# Alim.net
KiCad netlist of a schematic drawn in Altium Designer
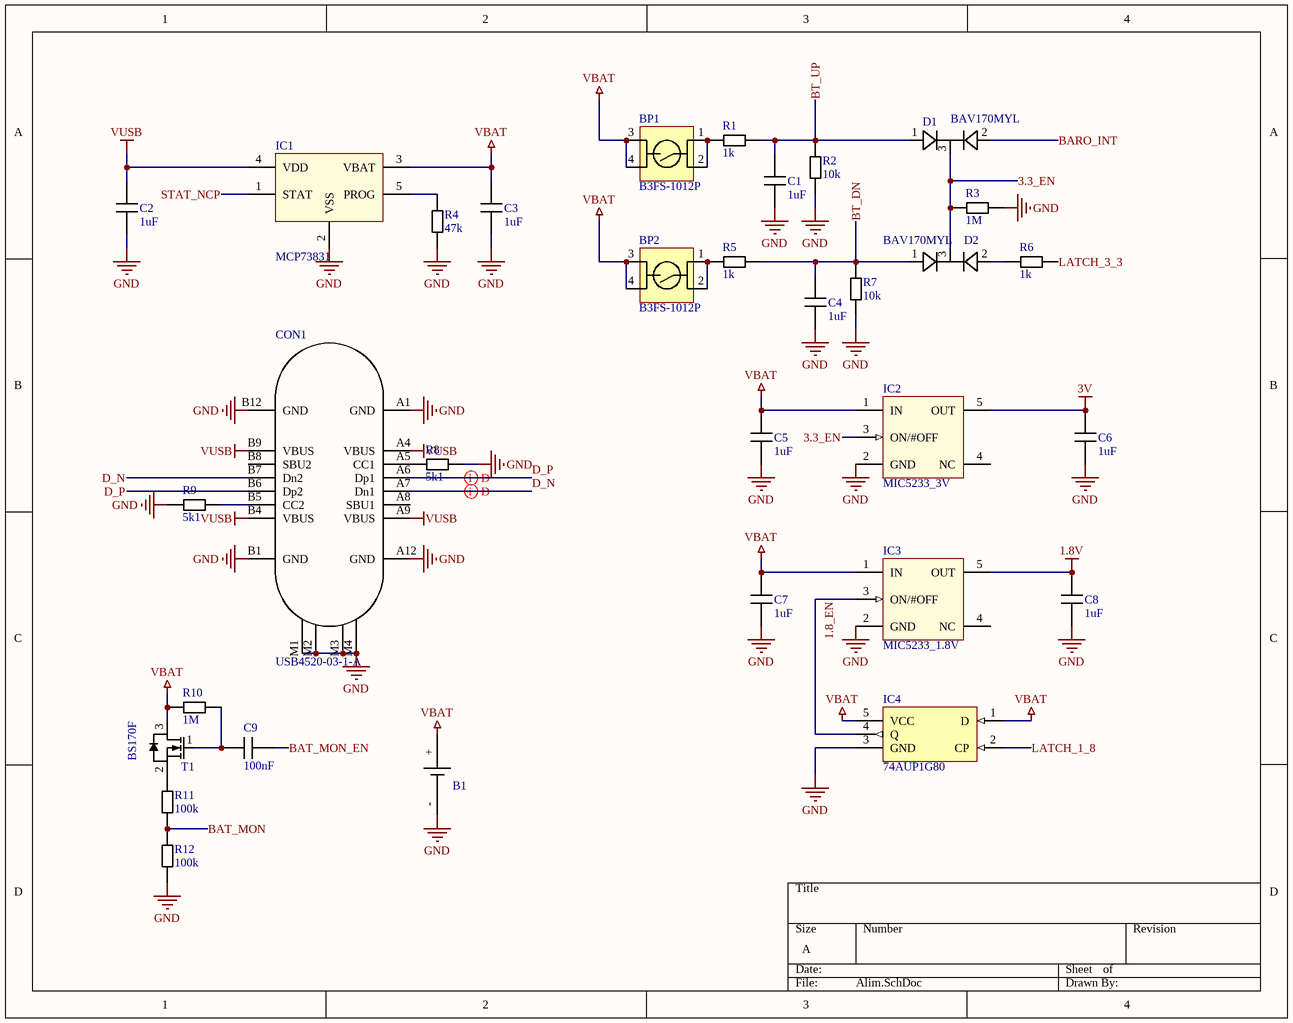
[diagram p0: Alim.SchDoc]

(export (version "E")
  (design (tool "Eeschema 10.0.6"))
  (components
    (comp (ref "B1")
      (value "EC382704P-T")
      (footprint "EC382704P-T")
      (description "2.3V 25mAh Li-ion")
      (libsource (lib "Battery") (part "EC382704P-T"))
    )
    (comp (ref "BP1") (value "B3FS-1012P") (footprint "B3FS") (libsource (lib "switch") (part "B3FS-1012P")))
    (comp (ref "BP2") (value "B3FS-1012P") (footprint "B3FS") (libsource (lib "switch") (part "B3FS-1012P")))
    (comp (ref "C1")
      (value "1uF")
      (footprint "C0402")
      (description "X7S 10% 0402 10V AEC-Q200")
      (fields (field (name "Comment") "1uF (0402) AEC-Q200"))
      (libsource (lib "Cap") (part "1uF (0402) AEC-Q200"))
    )
    (comp (ref "C2")
      (value "1uF")
      (footprint "C0402")
      (description "X7S 10% 0402 10V AEC-Q200")
      (fields (field (name "Comment") "1uF (0402) AEC-Q200"))
      (libsource (lib "Cap") (part "1uF (0402) AEC-Q200"))
    )
    (comp (ref "C3")
      (value "1uF")
      (footprint "C0402")
      (description "X7S 10% 0402 10V AEC-Q200")
      (fields (field (name "Comment") "1uF (0402) AEC-Q200"))
      (libsource (lib "Cap") (part "1uF (0402) AEC-Q200"))
    )
    (comp (ref "C4")
      (value "1uF")
      (footprint "C0402")
      (description "X7S 10% 0402 10V AEC-Q200")
      (fields (field (name "Comment") "1uF (0402) AEC-Q200"))
      (libsource (lib "Cap") (part "1uF (0402) AEC-Q200"))
    )
    (comp (ref "C5")
      (value "1uF")
      (footprint "C0402")
      (description "X7S 10% 0402 10V AEC-Q200")
      (fields (field (name "Comment") "1uF (0402) AEC-Q200"))
      (libsource (lib "Cap") (part "1uF (0402) AEC-Q200"))
    )
    (comp (ref "C6")
      (value "1uF")
      (footprint "C0402")
      (description "X7S 10% 0402 10V AEC-Q200")
      (fields (field (name "Comment") "1uF (0402) AEC-Q200"))
      (libsource (lib "Cap") (part "1uF (0402) AEC-Q200"))
    )
    (comp (ref "C7")
      (value "1uF")
      (footprint "C0402")
      (description "X7S 10% 0402 10V AEC-Q200")
      (fields (field (name "Comment") "1uF (0402) AEC-Q200"))
      (libsource (lib "Cap") (part "1uF (0402) AEC-Q200"))
    )
    (comp (ref "C8")
      (value "1uF")
      (footprint "C0402")
      (description "X7S 10% 0402 10V AEC-Q200")
      (fields (field (name "Comment") "1uF (0402) AEC-Q200"))
      (libsource (lib "Cap") (part "1uF (0402) AEC-Q200"))
    )
    (comp (ref "C9")
      (value "100nF")
      (footprint "C0402")
      (description "X7R 0402 10% 50V AEC-Q200")
      (fields (field (name "Comment") "100nF (0402) AEC-Q200"))
      (libsource (lib "Cap") (part "100nF (0402) AEC-Q200"))
    )
    (comp (ref "CON1")
      (value "USB4520-03-1-A")
      (footprint "USB4520-03-1-A")
      (description "Connecteur USB-C Receptacke mid PCB")
      (libsource (lib "ConnecteurAutre") (part "USB4520-03-1-A"))
    )
    (comp (ref "D1")
      (value "BAV170MYL")
      (footprint "DFN1006-3")
      (description "Diodes - General Purpose, Power, Switching BAV170M/SOT883/XQFN3")
      (libsource (lib "Diode") (part "BAV170MYL"))
    )
    (comp (ref "D2")
      (value "BAV170MYL")
      (footprint "DFN1006-3")
      (description "Diodes - General Purpose, Power, Switching BAV170M/SOT883/XQFN3")
      (libsource (lib "Diode") (part "BAV170MYL"))
    )
    (comp (ref "IC1")
      (value "MCP73831")
      (footprint "SOT23-5")
      (description "Chargeur Li-Ion/Li-Polymer")
      (libsource (lib "Charger") (part "MCP73831"))
    )
    (comp (ref "IC2")
      (value "MIC5233_3V")
      (footprint "SOT23-5")
      (description "3V Ζ SOT23 Ζ 100mA Ζ IN : 2.3V to 36V")
      (libsource (lib "Regul") (part "MIC5233_3V"))
    )
    (comp (ref "IC3")
      (value "MIC5233_1.8V")
      (footprint "SOT23-5")
      (description "1.8V Ζ SOT23 Ζ 100mA Ζ IN : 2.3V to 36V")
      (libsource (lib "Regul") (part "MIC5233_1.8V"))
    )
    (comp (ref "IC4")
      (value "74AUP1G80")
      (footprint "TSSOP5")
      (description "Low-power D-type flip-flop; positive-edge trigger TSSOP5")
      (libsource (lib "switch") (part "74AUP1G80"))
    )
    (comp (ref "R1")
      (value "1k")
      (footprint "R0402")
      (description "1% 0402 0.063W 100ppm")
      (fields (field (name "Comment") "1k (0402)"))
      (libsource (lib "Res") (part "1k (0402)"))
    )
    (comp (ref "R2")
      (value "10k")
      (footprint "R0402")
      (description "1% 0402 0.063W 100ppm")
      (fields (field (name "Comment") "10k (0402)"))
      (libsource (lib "Res") (part "10k (0402)"))
    )
    (comp (ref "R3")
      (value "1M")
      (footprint "R0402")
      (description "1% 0402 0.063W 100ppm")
      (fields (field (name "Comment") "1M (0402)"))
      (libsource (lib "Res") (part "1M (0402)"))
    )
    (comp (ref "R4")
      (value "47k")
      (footprint "R0402")
      (description "1% 0402 0.063W 100ppm")
      (fields (field (name "Comment") "47k (0402)"))
      (libsource (lib "Res") (part "47k (0402)"))
    )
    (comp (ref "R5")
      (value "1k")
      (footprint "R0402")
      (description "1% 0402 0.063W 100ppm")
      (fields (field (name "Comment") "1k (0402)"))
      (libsource (lib "Res") (part "1k (0402)"))
    )
    (comp (ref "R6")
      (value "1k")
      (footprint "R0402")
      (description "1% 0402 0.063W 100ppm")
      (fields (field (name "Comment") "1k (0402)"))
      (libsource (lib "Res") (part "1k (0402)"))
    )
    (comp (ref "R7")
      (value "10k")
      (footprint "R0402")
      (description "1% 0402 0.063W 100ppm")
      (fields (field (name "Comment") "10k (0402)"))
      (libsource (lib "Res") (part "10k (0402)"))
    )
    (comp (ref "R8")
      (value "5k1")
      (footprint "R0402")
      (description "1% 0402 0.1W 100ppm AEC-Q200")
      (fields (field (name "Comment") "5k1 (0402) AEC-Q200"))
      (libsource (lib "Res") (part "5k1 (0402) AEC-Q200"))
    )
    (comp (ref "R9")
      (value "5k1")
      (footprint "R0402")
      (description "1% 0402 0.1W 100ppm AEC-Q200")
      (fields (field (name "Comment") "5k1 (0402) AEC-Q200"))
      (libsource (lib "Res") (part "5k1 (0402) AEC-Q200"))
    )
    (comp (ref "R10")
      (value "1M")
      (footprint "R0402")
      (description "1% 0402 0.063W 100ppm")
      (fields (field (name "Comment") "1M (0402)"))
      (libsource (lib "Res") (part "1M (0402)"))
    )
    (comp (ref "R11")
      (value "100k")
      (footprint "R0402")
      (description "1% 0402  0.063W 100ppm")
      (fields (field (name "Comment") "100k (0402)"))
      (libsource (lib "Res") (part "100k (0402)"))
    )
    (comp (ref "R12")
      (value "100k")
      (footprint "R0402")
      (description "1% 0402  0.063W 100ppm")
      (fields (field (name "Comment") "100k (0402)"))
      (libsource (lib "Res") (part "100k (0402)"))
    )
    (comp (ref "T1")
      (value "BS170F")
      (footprint "SOT-23-3")
      (description "N-MOS Ζ SOT23 60V 150mA")
      (libsource (lib "Transistor") (part "BS170F"))
    )
  )
  (nets
    (net (code "2") (name "/3.3_EN") (class "Default")
      (node (ref "D1") (pin "3") (pinfunction "K1/A2_3") (pintype "passive"))
      (node (ref "D2") (pin "3") (pinfunction "K1/A2_3") (pintype "passive"))
      (node (ref "IC2") (pin "3") (pinfunction "ON/#OFF_3") (pintype "input"))
      (node (ref "R3") (pin "2") (pinfunction "2_2") (pintype "passive"))
    )
    (net (code "3") (name "/BARO_INT") (class "Default")
      (node (ref "D1") (pin "2") (pinfunction "K2_2") (pintype "passive"))
    )
    (net (code "4") (name "/BAT_MON") (class "Default")
      (node (ref "R11") (pin "1") (pinfunction "1_1") (pintype "passive"))
      (node (ref "R12") (pin "2") (pinfunction "2_2") (pintype "passive"))
    )
    (net (code "5") (name "/BAT_MON_EN") (class "Default")
      (node (ref "C9") (pin "1") (pinfunction "1_1") (pintype "passive"))
    )
    (net (code "6") (name "/BT_DN") (class "Default")
      (node (ref "C4") (pin "1") (pinfunction "1_1") (pintype "passive"))
      (node (ref "D2") (pin "1") (pinfunction "A1_1") (pintype "passive"))
      (node (ref "R5") (pin "2") (pinfunction "2_2") (pintype "passive"))
      (node (ref "R7") (pin "2") (pinfunction "2_2") (pintype "passive"))
    )
    (net (code "7") (name "/BT_UP") (class "Default")
      (node (ref "C1") (pin "1") (pinfunction "1_1") (pintype "passive"))
      (node (ref "D1") (pin "1") (pinfunction "A1_1") (pintype "passive"))
      (node (ref "R1") (pin "2") (pinfunction "2_2") (pintype "passive"))
      (node (ref "R2") (pin "2") (pinfunction "2_2") (pintype "passive"))
    )
    (net (code "8") (name "/D_N") (class "Default")
      (node (ref "CON1") (pin "A7") (pinfunction "Dn1_A7") (pintype "passive"))
      (node (ref "CON1") (pin "B7") (pinfunction "Dn2_B7") (pintype "passive"))
    )
    (net (code "9") (name "/D_P") (class "Default")
      (node (ref "CON1") (pin "A6") (pinfunction "Dp1_A6") (pintype "passive"))
      (node (ref "CON1") (pin "B6") (pinfunction "Dp2_B6") (pintype "passive"))
    )
    (net (code "10") (name "/LATCH_1_8") (class "Default")
      (node (ref "IC4") (pin "2") (pinfunction "CP_2") (pintype "input"))
    )
    (net (code "11") (name "/LATCH_3_3") (class "Default")
      (node (ref "R6") (pin "2") (pinfunction "2_2") (pintype "passive"))
    )
    (net (code "12") (name "/STAT_NCP") (class "Default")
      (node (ref "IC1") (pin "1") (pinfunction "STAT_1") (pintype "power_in"))
    )
    (net (code "13") (name "1.8V") (class "Default")
      (node (ref "C8") (pin "1") (pinfunction "1_1") (pintype "passive"))
      (node (ref "IC3") (pin "5") (pinfunction "OUT_5") (pintype "power_in"))
    )
    (net (code "14") (name "3V") (class "Default")
      (node (ref "C6") (pin "1") (pinfunction "1_1") (pintype "passive"))
      (node (ref "IC2") (pin "5") (pinfunction "OUT_5") (pintype "power_in"))
    )
    (net (code "15") (name "GND") (class "Default")
      (node (ref "B1") (pin "-") (pinfunction "-_-") (pintype "passive"))
      (node (ref "C1") (pin "2") (pinfunction "2_2") (pintype "passive"))
      (node (ref "C2") (pin "2") (pinfunction "2_2") (pintype "passive"))
      (node (ref "C3") (pin "2") (pinfunction "2_2") (pintype "passive"))
      (node (ref "C4") (pin "2") (pinfunction "2_2") (pintype "passive"))
      (node (ref "C5") (pin "2") (pinfunction "2_2") (pintype "passive"))
      (node (ref "C6") (pin "2") (pinfunction "2_2") (pintype "passive"))
      (node (ref "C7") (pin "2") (pinfunction "2_2") (pintype "passive"))
      (node (ref "C8") (pin "2") (pinfunction "2_2") (pintype "passive"))
      (node (ref "CON1") (pin "A1") (pinfunction "GND_A1") (pintype "passive"))
      (node (ref "CON1") (pin "A12") (pinfunction "GND_A12") (pintype "passive"))
      (node (ref "CON1") (pin "B1") (pinfunction "GND_B1") (pintype "passive"))
      (node (ref "CON1") (pin "B12") (pinfunction "GND_B12") (pintype "passive"))
      (node (ref "CON1") (pin "M1") (pintype "passive"))
      (node (ref "CON1") (pin "M2") (pintype "passive"))
      (node (ref "CON1") (pin "M3") (pintype "passive"))
      (node (ref "CON1") (pin "M4") (pintype "passive"))
      (node (ref "IC1") (pin "2") (pinfunction "VSS_2") (pintype "power_in"))
      (node (ref "IC2") (pin "2") (pinfunction "GND_2") (pintype "power_in"))
      (node (ref "IC3") (pin "2") (pinfunction "GND_2") (pintype "power_in"))
      (node (ref "IC4") (pin "3") (pinfunction "GND_3") (pintype "power_in"))
      (node (ref "R12") (pin "1") (pinfunction "1_1") (pintype "passive"))
      (node (ref "R2") (pin "1") (pinfunction "1_1") (pintype "passive"))
      (node (ref "R3") (pin "1") (pinfunction "1_1") (pintype "passive"))
      (node (ref "R4") (pin "1") (pinfunction "1_1") (pintype "passive"))
      (node (ref "R7") (pin "1") (pinfunction "1_1") (pintype "passive"))
      (node (ref "R8") (pin "2") (pinfunction "2_2") (pintype "passive"))
      (node (ref "R9") (pin "1") (pinfunction "1_1") (pintype "passive"))
    )
    (net (code "16") (name "Net-(BP1-Pad1)") (class "Default")
      (node (ref "BP1") (pin "1") (pinfunction "1_1") (pintype "passive"))
      (node (ref "BP1") (pin "2") (pinfunction "2_2") (pintype "passive"))
      (node (ref "R1") (pin "1") (pinfunction "1_1") (pintype "passive"))
    )
    (net (code "17") (name "Net-(BP2-Pad1)") (class "Default")
      (node (ref "BP2") (pin "1") (pinfunction "1_1") (pintype "passive"))
      (node (ref "BP2") (pin "2") (pinfunction "2_2") (pintype "passive"))
      (node (ref "R5") (pin "1") (pinfunction "1_1") (pintype "passive"))
    )
    (net (code "18") (name "Net-(CON1-CC1)") (class "Default")
      (node (ref "CON1") (pin "A5") (pinfunction "CC1_A5") (pintype "passive"))
      (node (ref "R8") (pin "1") (pinfunction "1_1") (pintype "passive"))
    )
    (net (code "19") (name "Net-(CON1-CC2)") (class "Default")
      (node (ref "CON1") (pin "B5") (pinfunction "CC2_B5") (pintype "passive"))
      (node (ref "R9") (pin "2") (pinfunction "2_2") (pintype "passive"))
    )
    (net (code "20") (name "Net-(D2-K2)") (class "Default")
      (node (ref "D2") (pin "2") (pinfunction "K2_2") (pintype "passive"))
      (node (ref "R6") (pin "1") (pinfunction "1_1") (pintype "passive"))
    )
    (net (code "21") (name "Net-(IC1-PROG)") (class "Default")
      (node (ref "IC1") (pin "5") (pinfunction "PROG_5") (pintype "power_in"))
      (node (ref "R4") (pin "2") (pinfunction "2_2") (pintype "passive"))
    )
    (net (code "22") (name "Net-(IC3-ON{slash}#OFF)") (class "Default")
      (node (ref "IC3") (pin "3") (pinfunction "ON/#OFF_3") (pintype "input"))
      (node (ref "IC4") (pin "4") (pinfunction "Q_4") (pintype "output"))
    )
    (net (code "23") (name "Net-(T1-G)") (class "Default")
      (node (ref "C9") (pin "2") (pinfunction "2_2") (pintype "passive"))
      (node (ref "R10") (pin "2") (pinfunction "2_2") (pintype "passive"))
      (node (ref "T1") (pin "1") (pinfunction "G_1") (pintype "passive"))
    )
    (net (code "24") (name "Net-(T1-S)") (class "Default")
      (node (ref "R11") (pin "2") (pinfunction "2_2") (pintype "passive"))
      (node (ref "T1") (pin "2") (pinfunction "S_2") (pintype "passive"))
    )
    (net (code "25") (name "VBAT") (class "Default")
      (node (ref "B1") (pin "+") (pinfunction "+_+") (pintype "passive"))
      (node (ref "BP1") (pin "3") (pinfunction "3_3") (pintype "passive"))
      (node (ref "BP1") (pin "4") (pinfunction "4_4") (pintype "passive"))
      (node (ref "BP2") (pin "3") (pinfunction "3_3") (pintype "passive"))
      (node (ref "BP2") (pin "4") (pinfunction "4_4") (pintype "passive"))
      (node (ref "C3") (pin "1") (pinfunction "1_1") (pintype "passive"))
      (node (ref "C5") (pin "1") (pinfunction "1_1") (pintype "passive"))
      (node (ref "C7") (pin "1") (pinfunction "1_1") (pintype "passive"))
      (node (ref "IC1") (pin "3") (pinfunction "VBAT_3") (pintype "power_in"))
      (node (ref "IC2") (pin "1") (pinfunction "IN_1") (pintype "power_in"))
      (node (ref "IC3") (pin "1") (pinfunction "IN_1") (pintype "power_in"))
      (node (ref "IC4") (pin "1") (pinfunction "D_1") (pintype "input"))
      (node (ref "IC4") (pin "5") (pinfunction "VCC_5") (pintype "power_in"))
      (node (ref "R10") (pin "1") (pinfunction "1_1") (pintype "passive"))
      (node (ref "T1") (pin "3") (pinfunction "D_3") (pintype "passive"))
    )
    (net (code "26") (name "VUSB") (class "Default")
      (node (ref "C2") (pin "1") (pinfunction "1_1") (pintype "passive"))
      (node (ref "CON1") (pin "A4") (pinfunction "VBUS_A4") (pintype "passive"))
      (node (ref "CON1") (pin "A9") (pinfunction "VBUS_A9") (pintype "passive"))
      (node (ref "CON1") (pin "B4") (pinfunction "VBUS_B4") (pintype "passive"))
      (node (ref "CON1") (pin "B9") (pinfunction "VBUS_B9") (pintype "passive"))
      (node (ref "IC1") (pin "4") (pinfunction "VDD_4") (pintype "power_in"))
    )
    (net (code "27") (name "unconnected-(CON1-SBU1-PadA8)") (class "Default")
      (node (ref "CON1") (pin "A8") (pinfunction "SBU1_A8") (pintype "passive"))
    )
    (net (code "28") (name "unconnected-(CON1-SBU2-PadB8)") (class "Default")
      (node (ref "CON1") (pin "B8") (pinfunction "SBU2_B8") (pintype "passive"))
    )
    (net (code "29") (name "unconnected-(IC2-NC-Pad4)") (class "Default")
      (node (ref "IC2") (pin "4") (pinfunction "NC_4") (pintype "passive"))
    )
    (net (code "30") (name "unconnected-(IC3-NC-Pad4)") (class "Default")
      (node (ref "IC3") (pin "4") (pinfunction "NC_4") (pintype "passive"))
    )
  )
)
